# MTQHub.net
KiCad netlist of a schematic drawn in EAGLE
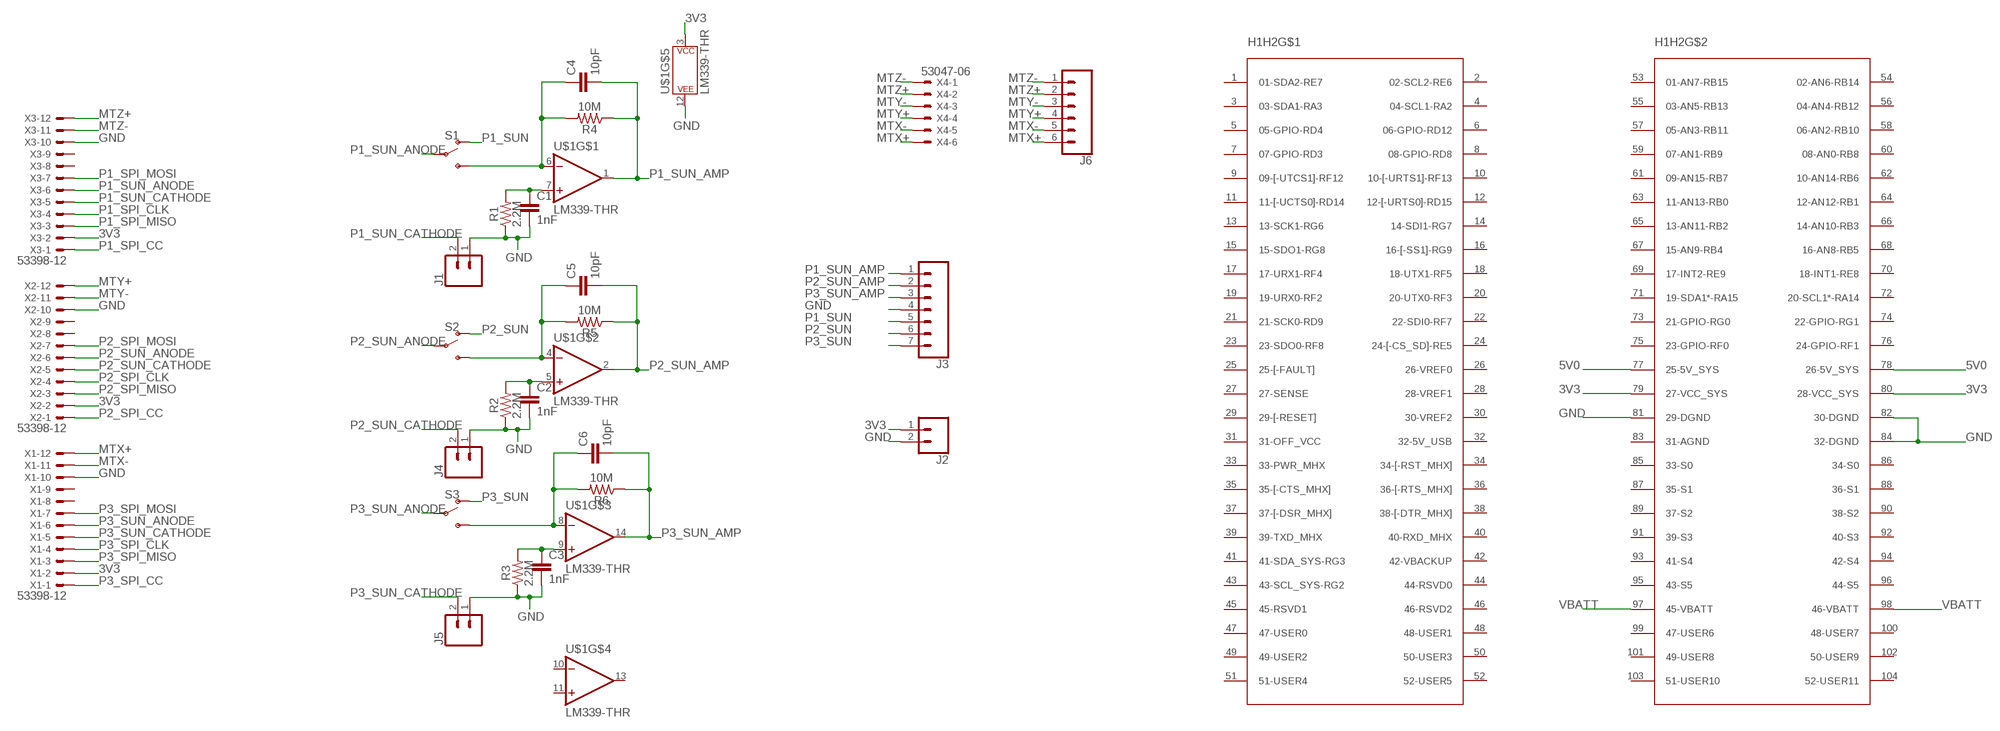
[diagram p0: schematic, sheet 1]

(export (version "E")
  (design (tool "Eeschema 10.0.6"))
  (components
    (comp (ref "C1")
      (value "1nF")
      (footprint "eagle-import:0603")
      (libsource (lib "eagle-import") (part "1.0NF/1000PF-0603-50V-10%"))
    )
    (comp (ref "C2")
      (value "1nF")
      (footprint "eagle-import:0603")
      (libsource (lib "eagle-import") (part "1.0NF/1000PF-0603-50V-10%"))
    )
    (comp (ref "C3")
      (value "1nF")
      (footprint "eagle-import:0603")
      (libsource (lib "eagle-import") (part "1.0NF/1000PF-0603-50V-10%"))
    )
    (comp (ref "C4")
      (value "10pF")
      (footprint "eagle-import:0603")
      (libsource (lib "eagle-import") (part "10PF-0603-50V-5%"))
    )
    (comp (ref "C5")
      (value "10pF")
      (footprint "eagle-import:0603")
      (libsource (lib "eagle-import") (part "10PF-0603-50V-5%"))
    )
    (comp (ref "C6")
      (value "10pF")
      (footprint "eagle-import:0603")
      (libsource (lib "eagle-import") (part "10PF-0603-50V-5%"))
    )
    (comp (ref "H1H2")
      (value "PC104_CONN")
      (footprint "eagle-import:PC_104")
      (libsource (lib "eagle-import") (part "PC104_CONN"))
    )
    (comp (ref "J1")
      (value "CONN_02")
      (footprint "eagle-import:1X02")
      (libsource (lib "eagle-import") (part "CONN_02"))
    )
    (comp (ref "J2")
      (value "CONN_02")
      (footprint "eagle-import:1X02")
      (libsource (lib "eagle-import") (part "CONN_02"))
    )
    (comp (ref "J3")
      (value "CONN_07")
      (footprint "eagle-import:1X07")
      (libsource (lib "eagle-import") (part "CONN_07"))
    )
    (comp (ref "J4")
      (value "CONN_02")
      (footprint "eagle-import:1X02")
      (libsource (lib "eagle-import") (part "CONN_02"))
    )
    (comp (ref "J5")
      (value "CONN_02")
      (footprint "eagle-import:1X02")
      (libsource (lib "eagle-import") (part "CONN_02"))
    )
    (comp (ref "J6")
      (value "CONN_06SILK_FEMALE_PTH")
      (footprint "eagle-import:1X06")
      (libsource (lib "eagle-import") (part "CONN_06SILK_FEMALE_PTH"))
    )
    (comp (ref "R1")
      (value "2.2M")
      (footprint "eagle-import:0603")
      (libsource (lib "eagle-import") (part "RESISTOR0603"))
    )
    (comp (ref "R2")
      (value "2.2M")
      (footprint "eagle-import:0603")
      (libsource (lib "eagle-import") (part "RESISTOR0603"))
    )
    (comp (ref "R3")
      (value "2.2M")
      (footprint "eagle-import:0603")
      (libsource (lib "eagle-import") (part "RESISTOR0603"))
    )
    (comp (ref "R4")
      (value "10M")
      (footprint "eagle-import:0603")
      (libsource (lib "eagle-import") (part "RESISTOR0603"))
    )
    (comp (ref "R5")
      (value "10M")
      (footprint "eagle-import:0603")
      (libsource (lib "eagle-import") (part "RESISTOR0603"))
    )
    (comp (ref "R6")
      (value "10M")
      (footprint "eagle-import:0603")
      (libsource (lib "eagle-import") (part "RESISTOR0603"))
    )
    (comp (ref "S1")
      (value "SWITCH-SPDT-PTH-11.6X4.0MM")
      (footprint "eagle-import:SWITCH_SPDT_PTH_11.6X4.0MM")
      (libsource (lib "eagle-import") (part "SWITCH-SPDT-PTH-11.6X4.0MM"))
    )
    (comp (ref "S2")
      (value "SWITCH-SPDT-PTH-11.6X4.0MM")
      (footprint "eagle-import:SWITCH_SPDT_PTH_11.6X4.0MM")
      (libsource (lib "eagle-import") (part "SWITCH-SPDT-PTH-11.6X4.0MM"))
    )
    (comp (ref "S3")
      (value "SWITCH-SPDT-PTH-11.6X4.0MM")
      (footprint "eagle-import:SWITCH_SPDT_PTH_11.6X4.0MM")
      (libsource (lib "eagle-import") (part "SWITCH-SPDT-PTH-11.6X4.0MM"))
    )
    (comp (ref "U$1")
      (value "LM339-THR")
      (footprint "eagle-import:DIL14")
      (libsource (lib "eagle-import") (part "LM339-THR"))
    )
    (comp (ref "X1")
      (value "53398-12")
      (footprint "eagle-import:53398-12")
      (fields (field (name "MF") "MOLEX"))
      (libsource (lib "eagle-import") (part "53?-12398"))
    )
    (comp (ref "X2")
      (value "53398-12")
      (footprint "eagle-import:53398-12")
      (fields (field (name "MF") "MOLEX"))
      (libsource (lib "eagle-import") (part "53?-12398"))
    )
    (comp (ref "X3")
      (value "53398-12")
      (footprint "eagle-import:53398-12")
      (fields (field (name "MF") "MOLEX"))
      (libsource (lib "eagle-import") (part "53?-12398"))
    )
    (comp (ref "X4")
      (value "53047-06")
      (footprint "eagle-import:53047-06")
      (fields (field (name "MF") "MOLEX") (field (name "MPN") "53047-0610-C"))
      (libsource (lib "eagle-import") (part "53?-06047"))
    )
  )
  (nets
    (net (code "1") (name "/3V3") (class "Default")
      (node (ref "H1H2") (pin "79") (pinfunction "27-VCC_SYS_79") (pintype "bidirectional"))
      (node (ref "H1H2") (pin "80") (pinfunction "28-VCC_SYS_80") (pintype "bidirectional"))
      (node (ref "J2") (pin "1") (pinfunction "1_1") (pintype "passive"))
      (node (ref "U$1") (pin "3") (pinfunction "P$V+_3") (pintype "bidirectional"))
      (node (ref "X1") (pin "2") (pinfunction "S_2") (pintype "passive"))
      (node (ref "X2") (pin "2") (pinfunction "S_2") (pintype "passive"))
      (node (ref "X3") (pin "2") (pinfunction "S_2") (pintype "passive"))
    )
    (net (code "2") (name "/5V0") (class "Default")
      (node (ref "H1H2") (pin "77") (pinfunction "25-5V_SYS_77") (pintype "bidirectional"))
      (node (ref "H1H2") (pin "78") (pinfunction "26-5V_SYS_78") (pintype "bidirectional"))
    )
    (net (code "3") (name "/GND") (class "Default")
      (node (ref "C1") (pin "2") (pinfunction "2_2") (pintype "passive"))
      (node (ref "C2") (pin "2") (pinfunction "2_2") (pintype "passive"))
      (node (ref "C3") (pin "2") (pinfunction "2_2") (pintype "passive"))
      (node (ref "H1H2") (pin "81") (pinfunction "29-DGND_81") (pintype "bidirectional"))
      (node (ref "H1H2") (pin "82") (pinfunction "30-DGND_82") (pintype "bidirectional"))
      (node (ref "H1H2") (pin "84") (pinfunction "32-DGND_84") (pintype "bidirectional"))
      (node (ref "J1") (pin "1") (pinfunction "1_1") (pintype "passive"))
      (node (ref "J2") (pin "2") (pinfunction "2_2") (pintype "passive"))
      (node (ref "J3") (pin "4") (pinfunction "4_4") (pintype "passive"))
      (node (ref "J4") (pin "1") (pinfunction "1_1") (pintype "passive"))
      (node (ref "J5") (pin "1") (pinfunction "1_1") (pintype "passive"))
      (node (ref "R1") (pin "1") (pinfunction "1_1") (pintype "passive"))
      (node (ref "R2") (pin "1") (pinfunction "1_1") (pintype "passive"))
      (node (ref "R3") (pin "1") (pinfunction "1_1") (pintype "passive"))
      (node (ref "U$1") (pin "12") (pinfunction "P$V-_12") (pintype "bidirectional"))
      (node (ref "X1") (pin "10") (pinfunction "S_10") (pintype "passive"))
      (node (ref "X2") (pin "10") (pinfunction "S_10") (pintype "passive"))
      (node (ref "X3") (pin "10") (pinfunction "S_10") (pintype "passive"))
    )
    (net (code "4") (name "/MTX+") (class "Default")
      (node (ref "J6") (pin "6") (pinfunction "6_6") (pintype "passive"))
      (node (ref "X1") (pin "12") (pinfunction "S_12") (pintype "passive"))
      (node (ref "X4") (pin "6") (pinfunction "S_6") (pintype "passive"))
    )
    (net (code "5") (name "/MTX-") (class "Default")
      (node (ref "J6") (pin "5") (pinfunction "5_5") (pintype "passive"))
      (node (ref "X1") (pin "11") (pinfunction "S_11") (pintype "passive"))
      (node (ref "X4") (pin "5") (pinfunction "S_5") (pintype "passive"))
    )
    (net (code "6") (name "/MTY+") (class "Default")
      (node (ref "J6") (pin "4") (pinfunction "4_4") (pintype "passive"))
      (node (ref "X2") (pin "12") (pinfunction "S_12") (pintype "passive"))
      (node (ref "X4") (pin "4") (pinfunction "S_4") (pintype "passive"))
    )
    (net (code "7") (name "/MTY-") (class "Default")
      (node (ref "J6") (pin "3") (pinfunction "3_3") (pintype "passive"))
      (node (ref "X2") (pin "11") (pinfunction "S_11") (pintype "passive"))
      (node (ref "X4") (pin "3") (pinfunction "S_3") (pintype "passive"))
    )
    (net (code "8") (name "/MTZ+") (class "Default")
      (node (ref "J6") (pin "2") (pinfunction "2_2") (pintype "passive"))
      (node (ref "X3") (pin "12") (pinfunction "S_12") (pintype "passive"))
      (node (ref "X4") (pin "2") (pinfunction "S_2") (pintype "passive"))
    )
    (net (code "9") (name "/MTZ-") (class "Default")
      (node (ref "J6") (pin "1") (pinfunction "1_1") (pintype "passive"))
      (node (ref "X3") (pin "11") (pinfunction "S_11") (pintype "passive"))
      (node (ref "X4") (pin "1") (pinfunction "S_1") (pintype "passive"))
    )
    (net (code "10") (name "/P1_SPI_CC") (class "Default")
      (node (ref "X3") (pin "1") (pinfunction "S_1") (pintype "passive"))
    )
    (net (code "11") (name "/P1_SPI_CLK") (class "Default")
      (node (ref "X3") (pin "4") (pinfunction "S_4") (pintype "passive"))
    )
    (net (code "12") (name "/P1_SPI_MISO") (class "Default")
      (node (ref "X3") (pin "3") (pinfunction "S_3") (pintype "passive"))
    )
    (net (code "13") (name "/P1_SPI_MOSI") (class "Default")
      (node (ref "X3") (pin "7") (pinfunction "S_7") (pintype "passive"))
    )
    (net (code "14") (name "/P1_SUN") (class "Default")
      (node (ref "J3") (pin "5") (pinfunction "5_5") (pintype "passive"))
      (node (ref "S1") (pin "1") (pinfunction "O_1") (pintype "passive"))
    )
    (net (code "15") (name "/P1_SUN_AMP") (class "Default")
      (node (ref "C4") (pin "2") (pinfunction "2_2") (pintype "passive"))
      (node (ref "J3") (pin "1") (pinfunction "1_1") (pintype "passive"))
      (node (ref "R4") (pin "1") (pinfunction "1_1") (pintype "passive"))
      (node (ref "U$1") (pin "1") (pinfunction "OUT_1") (pintype "output"))
    )
    (net (code "16") (name "/P1_SUN_ANODE") (class "Default")
      (node (ref "S1") (pin "2") (pinfunction "P_2") (pintype "passive"))
      (node (ref "X3") (pin "6") (pinfunction "S_6") (pintype "passive"))
    )
    (net (code "17") (name "/P1_SUN_CATHODE") (class "Default")
      (node (ref "J1") (pin "2") (pinfunction "2_2") (pintype "passive"))
      (node (ref "X3") (pin "5") (pinfunction "S_5") (pintype "passive"))
    )
    (net (code "18") (name "/P2_SPI_CC") (class "Default")
      (node (ref "X2") (pin "1") (pinfunction "S_1") (pintype "passive"))
    )
    (net (code "19") (name "/P2_SPI_CLK") (class "Default")
      (node (ref "X2") (pin "4") (pinfunction "S_4") (pintype "passive"))
    )
    (net (code "20") (name "/P2_SPI_MISO") (class "Default")
      (node (ref "X2") (pin "3") (pinfunction "S_3") (pintype "passive"))
    )
    (net (code "21") (name "/P2_SPI_MOSI") (class "Default")
      (node (ref "X2") (pin "7") (pinfunction "S_7") (pintype "passive"))
    )
    (net (code "22") (name "/P2_SUN") (class "Default")
      (node (ref "J3") (pin "6") (pinfunction "6_6") (pintype "passive"))
      (node (ref "S2") (pin "1") (pinfunction "O_1") (pintype "passive"))
    )
    (net (code "23") (name "/P2_SUN_AMP") (class "Default")
      (node (ref "C5") (pin "2") (pinfunction "2_2") (pintype "passive"))
      (node (ref "J3") (pin "2") (pinfunction "2_2") (pintype "passive"))
      (node (ref "R5") (pin "1") (pinfunction "1_1") (pintype "passive"))
      (node (ref "U$1") (pin "2") (pinfunction "OUT_2") (pintype "output"))
    )
    (net (code "24") (name "/P2_SUN_ANODE") (class "Default")
      (node (ref "S2") (pin "2") (pinfunction "P_2") (pintype "passive"))
      (node (ref "X2") (pin "6") (pinfunction "S_6") (pintype "passive"))
    )
    (net (code "25") (name "/P2_SUN_CATHODE") (class "Default")
      (node (ref "J4") (pin "2") (pinfunction "2_2") (pintype "passive"))
      (node (ref "X2") (pin "5") (pinfunction "S_5") (pintype "passive"))
    )
    (net (code "26") (name "/P3_SPI_CC") (class "Default")
      (node (ref "X1") (pin "1") (pinfunction "S_1") (pintype "passive"))
    )
    (net (code "27") (name "/P3_SPI_CLK") (class "Default")
      (node (ref "X1") (pin "4") (pinfunction "S_4") (pintype "passive"))
    )
    (net (code "28") (name "/P3_SPI_MISO") (class "Default")
      (node (ref "X1") (pin "3") (pinfunction "S_3") (pintype "passive"))
    )
    (net (code "29") (name "/P3_SPI_MOSI") (class "Default")
      (node (ref "X1") (pin "7") (pinfunction "S_7") (pintype "passive"))
    )
    (net (code "30") (name "/P3_SUN") (class "Default")
      (node (ref "J3") (pin "7") (pinfunction "7_7") (pintype "passive"))
      (node (ref "S3") (pin "1") (pinfunction "O_1") (pintype "passive"))
    )
    (net (code "31") (name "/P3_SUN_AMP") (class "Default")
      (node (ref "C6") (pin "2") (pinfunction "2_2") (pintype "passive"))
      (node (ref "J3") (pin "3") (pinfunction "3_3") (pintype "passive"))
      (node (ref "R6") (pin "1") (pinfunction "1_1") (pintype "passive"))
      (node (ref "U$1") (pin "14") (pinfunction "OUT_14") (pintype "output"))
    )
    (net (code "32") (name "/P3_SUN_ANODE") (class "Default")
      (node (ref "S3") (pin "2") (pinfunction "P_2") (pintype "passive"))
      (node (ref "X1") (pin "6") (pinfunction "S_6") (pintype "passive"))
    )
    (net (code "33") (name "/P3_SUN_CATHODE") (class "Default")
      (node (ref "J5") (pin "2") (pinfunction "2_2") (pintype "passive"))
      (node (ref "X1") (pin "5") (pinfunction "S_5") (pintype "passive"))
    )
    (net (code "34") (name "/VBATT") (class "Default")
      (node (ref "H1H2") (pin "97") (pinfunction "45-VBATT_97") (pintype "bidirectional"))
      (node (ref "H1H2") (pin "98") (pinfunction "46-VBATT_98") (pintype "bidirectional"))
    )
    (net (code "35") (name "Net-(S1-S)") (class "Default")
      (node (ref "C4") (pin "1") (pinfunction "1_1") (pintype "passive"))
      (node (ref "R4") (pin "2") (pinfunction "2_2") (pintype "passive"))
      (node (ref "S1") (pin "3") (pinfunction "S_3") (pintype "passive"))
      (node (ref "U$1") (pin "6") (pinfunction "-IN_6") (pintype "input"))
    )
    (net (code "36") (name "Net-(S2-S)") (class "Default")
      (node (ref "C5") (pin "1") (pinfunction "1_1") (pintype "passive"))
      (node (ref "R5") (pin "2") (pinfunction "2_2") (pintype "passive"))
      (node (ref "S2") (pin "3") (pinfunction "S_3") (pintype "passive"))
      (node (ref "U$1") (pin "4") (pinfunction "-IN_4") (pintype "input"))
    )
    (net (code "37") (name "Net-(S3-S)") (class "Default")
      (node (ref "C6") (pin "1") (pinfunction "1_1") (pintype "passive"))
      (node (ref "R6") (pin "2") (pinfunction "2_2") (pintype "passive"))
      (node (ref "S3") (pin "3") (pinfunction "S_3") (pintype "passive"))
      (node (ref "U$1") (pin "8") (pinfunction "-IN_8") (pintype "input"))
    )
    (net (code "38") (name "Net-(U$1A-+IN)") (class "Default")
      (node (ref "C1") (pin "1") (pinfunction "1_1") (pintype "passive"))
      (node (ref "R1") (pin "2") (pinfunction "2_2") (pintype "passive"))
      (node (ref "U$1") (pin "7") (pinfunction "+IN_7") (pintype "input"))
    )
    (net (code "39") (name "Net-(U$1B-+IN)") (class "Default")
      (node (ref "C2") (pin "1") (pinfunction "1_1") (pintype "passive"))
      (node (ref "R2") (pin "2") (pinfunction "2_2") (pintype "passive"))
      (node (ref "U$1") (pin "5") (pinfunction "+IN_5") (pintype "input"))
    )
    (net (code "40") (name "Net-(U$1C-+IN)") (class "Default")
      (node (ref "C3") (pin "1") (pinfunction "1_1") (pintype "passive"))
      (node (ref "R3") (pin "2") (pinfunction "2_2") (pintype "passive"))
      (node (ref "U$1") (pin "9") (pinfunction "+IN_9") (pintype "input"))
    )
    (net (code "41") (name "unconnected-(H1H2A-01-SDA2-RE7-Pad1)") (class "Default")
      (node (ref "H1H2") (pin "1") (pinfunction "01-SDA2-RE7_1") (pintype "bidirectional"))
    )
    (net (code "42") (name "unconnected-(H1H2A-02-SCL2-RE6-Pad2)") (class "Default")
      (node (ref "H1H2") (pin "2") (pinfunction "02-SCL2-RE6_2") (pintype "bidirectional"))
    )
    (net (code "43") (name "unconnected-(H1H2A-03-SDA1-RA3-Pad3)") (class "Default")
      (node (ref "H1H2") (pin "3") (pinfunction "03-SDA1-RA3_3") (pintype "bidirectional"))
    )
    (net (code "44") (name "unconnected-(H1H2A-04-SCL1-RA2-Pad4)") (class "Default")
      (node (ref "H1H2") (pin "4") (pinfunction "04-SCL1-RA2_4") (pintype "bidirectional"))
    )
    (net (code "45") (name "unconnected-(H1H2A-05-GPIO-RD4-Pad5)") (class "Default")
      (node (ref "H1H2") (pin "5") (pinfunction "05-GPIO-RD4_5") (pintype "bidirectional"))
    )
    (net (code "46") (name "unconnected-(H1H2A-06-GPIO-RD12-Pad6)") (class "Default")
      (node (ref "H1H2") (pin "6") (pinfunction "06-GPIO-RD12_6") (pintype "bidirectional"))
    )
    (net (code "47") (name "unconnected-(H1H2A-07-GPIO-RD3-Pad7)") (class "Default")
      (node (ref "H1H2") (pin "7") (pinfunction "07-GPIO-RD3_7") (pintype "bidirectional"))
    )
    (net (code "48") (name "unconnected-(H1H2A-08-GPIO-RD8-Pad8)") (class "Default")
      (node (ref "H1H2") (pin "8") (pinfunction "08-GPIO-RD8_8") (pintype "bidirectional"))
    )
    (net (code "49") (name "unconnected-(H1H2A-09-[-UTCS1]-RF12-Pad9)") (class "Default")
      (node (ref "H1H2") (pin "9") (pinfunction "09-[-UTCS1]-RF12_9") (pintype "bidirectional"))
    )
    (net (code "50") (name "unconnected-(H1H2A-10-[-URTS1]-RF13-Pad10)") (class "Default")
      (node (ref "H1H2") (pin "10") (pinfunction "10-[-URTS1]-RF13_10") (pintype "bidirectional"))
    )
    (net (code "51") (name "unconnected-(H1H2A-11-[-UCTS0]-RD14-Pad11)") (class "Default")
      (node (ref "H1H2") (pin "11") (pinfunction "11-[-UCTS0]-RD14_11") (pintype "bidirectional"))
    )
    (net (code "52") (name "unconnected-(H1H2A-12-[-URTS0]-RD15-Pad12)") (class "Default")
      (node (ref "H1H2") (pin "12") (pinfunction "12-[-URTS0]-RD15_12") (pintype "bidirectional"))
    )
    (net (code "53") (name "unconnected-(H1H2A-13-SCK1-RG6-Pad13)") (class "Default")
      (node (ref "H1H2") (pin "13") (pinfunction "13-SCK1-RG6_13") (pintype "bidirectional"))
    )
    (net (code "54") (name "unconnected-(H1H2A-14-SDI1-RG7-Pad14)") (class "Default")
      (node (ref "H1H2") (pin "14") (pinfunction "14-SDI1-RG7_14") (pintype "bidirectional"))
    )
    (net (code "55") (name "unconnected-(H1H2A-15-SDO1-RG8-Pad15)") (class "Default")
      (node (ref "H1H2") (pin "15") (pinfunction "15-SDO1-RG8_15") (pintype "bidirectional"))
    )
    (net (code "56") (name "unconnected-(H1H2A-16-[-SS1]-RG9-Pad16)") (class "Default")
      (node (ref "H1H2") (pin "16") (pinfunction "16-[-SS1]-RG9_16") (pintype "bidirectional"))
    )
    (net (code "57") (name "unconnected-(H1H2A-17-URX1-RF4-Pad17)") (class "Default")
      (node (ref "H1H2") (pin "17") (pinfunction "17-URX1-RF4_17") (pintype "bidirectional"))
    )
    (net (code "58") (name "unconnected-(H1H2A-18-UTX1-RF5-Pad18)") (class "Default")
      (node (ref "H1H2") (pin "18") (pinfunction "18-UTX1-RF5_18") (pintype "bidirectional"))
    )
    (net (code "59") (name "unconnected-(H1H2A-19-URX0-RF2-Pad19)") (class "Default")
      (node (ref "H1H2") (pin "19") (pinfunction "19-URX0-RF2_19") (pintype "bidirectional"))
    )
    (net (code "60") (name "unconnected-(H1H2A-20-UTX0-RF3-Pad20)") (class "Default")
      (node (ref "H1H2") (pin "20") (pinfunction "20-UTX0-RF3_20") (pintype "bidirectional"))
    )
    (net (code "61") (name "unconnected-(H1H2A-21-SCK0-RD9-Pad21)") (class "Default")
      (node (ref "H1H2") (pin "21") (pinfunction "21-SCK0-RD9_21") (pintype "bidirectional"))
    )
    (net (code "62") (name "unconnected-(H1H2A-22-SDI0-RF7-Pad22)") (class "Default")
      (node (ref "H1H2") (pin "22") (pinfunction "22-SDI0-RF7_22") (pintype "bidirectional"))
    )
    (net (code "63") (name "unconnected-(H1H2A-23-SDO0-RF8-Pad23)") (class "Default")
      (node (ref "H1H2") (pin "23") (pinfunction "23-SDO0-RF8_23") (pintype "bidirectional"))
    )
    (net (code "64") (name "unconnected-(H1H2A-24-[-CS_SD]-RE5-Pad24)") (class "Default")
      (node (ref "H1H2") (pin "24") (pinfunction "24-[-CS_SD]-RE5_24") (pintype "bidirectional"))
    )
    (net (code "65") (name "unconnected-(H1H2A-25-[-FAULT]-Pad25)") (class "Default")
      (node (ref "H1H2") (pin "25") (pinfunction "25-[-FAULT]_25") (pintype "bidirectional"))
    )
    (net (code "66") (name "unconnected-(H1H2A-26-VREF0-Pad26)") (class "Default")
      (node (ref "H1H2") (pin "26") (pinfunction "26-VREF0_26") (pintype "bidirectional"))
    )
    (net (code "67") (name "unconnected-(H1H2A-27-SENSE-Pad27)") (class "Default")
      (node (ref "H1H2") (pin "27") (pinfunction "27-SENSE_27") (pintype "bidirectional"))
    )
    (net (code "68") (name "unconnected-(H1H2A-28-VREF1-Pad28)") (class "Default")
      (node (ref "H1H2") (pin "28") (pinfunction "28-VREF1_28") (pintype "bidirectional"))
    )
    (net (code "69") (name "unconnected-(H1H2A-29-[-RESET]-Pad29)") (class "Default")
      (node (ref "H1H2") (pin "29") (pinfunction "29-[-RESET]_29") (pintype "bidirectional"))
    )
    (net (code "70") (name "unconnected-(H1H2A-30-VREF2-Pad30)") (class "Default")
      (node (ref "H1H2") (pin "30") (pinfunction "30-VREF2_30") (pintype "bidirectional"))
    )
    (net (code "71") (name "unconnected-(H1H2A-31-OFF_VCC-Pad31)") (class "Default")
      (node (ref "H1H2") (pin "31") (pinfunction "31-OFF_VCC_31") (pintype "bidirectional"))
    )
    (net (code "72") (name "unconnected-(H1H2A-32-5V_USB-Pad32)") (class "Default")
      (node (ref "H1H2") (pin "32") (pinfunction "32-5V_USB_32") (pintype "bidirectional"))
    )
    (net (code "73") (name "unconnected-(H1H2A-33-PWR_MHX-Pad33)") (class "Default")
      (node (ref "H1H2") (pin "33") (pinfunction "33-PWR_MHX_33") (pintype "bidirectional"))
    )
    (net (code "74") (name "unconnected-(H1H2A-34-[-RST_MHX]-Pad34)") (class "Default")
      (node (ref "H1H2") (pin "34") (pinfunction "34-[-RST_MHX]_34") (pintype "bidirectional"))
    )
    (net (code "75") (name "unconnected-(H1H2A-35-[-CTS_MHX]-Pad35)") (class "Default")
      (node (ref "H1H2") (pin "35") (pinfunction "35-[-CTS_MHX]_35") (pintype "bidirectional"))
    )
    (net (code "76") (name "unconnected-(H1H2A-36-[-RTS_MHX]-Pad36)") (class "Default")
      (node (ref "H1H2") (pin "36") (pinfunction "36-[-RTS_MHX]_36") (pintype "bidirectional"))
    )
    (net (code "77") (name "unconnected-(H1H2A-37-[-DSR_MHX]-Pad37)") (class "Default")
      (node (ref "H1H2") (pin "37") (pinfunction "37-[-DSR_MHX]_37") (pintype "bidirectional"))
    )
    (net (code "78") (name "unconnected-(H1H2A-38-[-DTR_MHX]-Pad38)") (class "Default")
      (node (ref "H1H2") (pin "38") (pinfunction "38-[-DTR_MHX]_38") (pintype "bidirectional"))
    )
    (net (code "79") (name "unconnected-(H1H2A-39-TXD_MHX-Pad39)") (class "Default")
      (node (ref "H1H2") (pin "39") (pinfunction "39-TXD_MHX_39") (pintype "bidirectional"))
    )
    (net (code "80") (name "unconnected-(H1H2A-40-RXD_MHX-Pad40)") (class "Default")
      (node (ref "H1H2") (pin "40") (pinfunction "40-RXD_MHX_40") (pintype "bidirectional"))
    )
    (net (code "81") (name "unconnected-(H1H2A-41-SDA_SYS-RG3-Pad41)") (class "Default")
      (node (ref "H1H2") (pin "41") (pinfunction "41-SDA_SYS-RG3_41") (pintype "bidirectional"))
    )
    (net (code "82") (name "unconnected-(H1H2A-42-VBACKUP-Pad42)") (class "Default")
      (node (ref "H1H2") (pin "42") (pinfunction "42-VBACKUP_42") (pintype "bidirectional"))
    )
    (net (code "83") (name "unconnected-(H1H2A-43-SCL_SYS-RG2-Pad43)") (class "Default")
      (node (ref "H1H2") (pin "43") (pinfunction "43-SCL_SYS-RG2_43") (pintype "bidirectional"))
    )
    (net (code "84") (name "unconnected-(H1H2A-44-RSVD0-Pad44)") (class "Default")
      (node (ref "H1H2") (pin "44") (pinfunction "44-RSVD0_44") (pintype "bidirectional"))
    )
    (net (code "85") (name "unconnected-(H1H2A-45-RSVD1-Pad45)") (class "Default")
      (node (ref "H1H2") (pin "45") (pinfunction "45-RSVD1_45") (pintype "bidirectional"))
    )
    (net (code "86") (name "unconnected-(H1H2A-46-RSVD2-Pad46)") (class "Default")
      (node (ref "H1H2") (pin "46") (pinfunction "46-RSVD2_46") (pintype "bidirectional"))
    )
    (net (code "87") (name "unconnected-(H1H2A-47-USER0-Pad47)") (class "Default")
      (node (ref "H1H2") (pin "47") (pinfunction "47-USER0_47") (pintype "bidirectional"))
    )
    (net (code "88") (name "unconnected-(H1H2A-48-USER1-Pad48)") (class "Default")
      (node (ref "H1H2") (pin "48") (pinfunction "48-USER1_48") (pintype "bidirectional"))
    )
    (net (code "89") (name "unconnected-(H1H2A-49-USER2-Pad49)") (class "Default")
      (node (ref "H1H2") (pin "49") (pinfunction "49-USER2_49") (pintype "bidirectional"))
    )
    (net (code "90") (name "unconnected-(H1H2A-50-USER3-Pad50)") (class "Default")
      (node (ref "H1H2") (pin "50") (pinfunction "50-USER3_50") (pintype "bidirectional"))
    )
    (net (code "91") (name "unconnected-(H1H2A-51-USER4-Pad51)") (class "Default")
      (node (ref "H1H2") (pin "51") (pinfunction "51-USER4_51") (pintype "bidirectional"))
    )
    (net (code "92") (name "unconnected-(H1H2A-52-USER5-Pad52)") (class "Default")
      (node (ref "H1H2") (pin "52") (pinfunction "52-USER5_52") (pintype "bidirectional"))
    )
    (net (code "93") (name "unconnected-(H1H2B-01-AN7-RB15-Pad53)") (class "Default")
      (node (ref "H1H2") (pin "53") (pinfunction "01-AN7-RB15_53") (pintype "bidirectional"))
    )
    (net (code "94") (name "unconnected-(H1H2B-02-AN6-RB14-Pad54)") (class "Default")
      (node (ref "H1H2") (pin "54") (pinfunction "02-AN6-RB14_54") (pintype "bidirectional"))
    )
    (net (code "95") (name "unconnected-(H1H2B-03-AN5-RB13-Pad55)") (class "Default")
      (node (ref "H1H2") (pin "55") (pinfunction "03-AN5-RB13_55") (pintype "bidirectional"))
    )
    (net (code "96") (name "unconnected-(H1H2B-04-AN4-RB12-Pad56)") (class "Default")
      (node (ref "H1H2") (pin "56") (pinfunction "04-AN4-RB12_56") (pintype "bidirectional"))
    )
    (net (code "97") (name "unconnected-(H1H2B-05-AN3-RB11-Pad57)") (class "Default")
      (node (ref "H1H2") (pin "57") (pinfunction "05-AN3-RB11_57") (pintype "bidirectional"))
    )
    (net (code "98") (name "unconnected-(H1H2B-06-AN2-RB10-Pad58)") (class "Default")
      (node (ref "H1H2") (pin "58") (pinfunction "06-AN2-RB10_58") (pintype "bidirectional"))
    )
    (net (code "99") (name "unconnected-(H1H2B-07-AN1-RB9-Pad59)") (class "Default")
      (node (ref "H1H2") (pin "59") (pinfunction "07-AN1-RB9_59") (pintype "bidirectional"))
    )
    (net (code "100") (name "unconnected-(H1H2B-08-AN0-RB8-Pad60)") (class "Default")
      (node (ref "H1H2") (pin "60") (pinfunction "08-AN0-RB8_60") (pintype "bidirectional"))
    )
    (net (code "101") (name "unconnected-(H1H2B-09-AN15-RB7-Pad61)") (class "Default")
      (node (ref "H1H2") (pin "61") (pinfunction "09-AN15-RB7_61") (pintype "bidirectional"))
    )
    (net (code "102") (name "unconnected-(H1H2B-10-AN14-RB6-Pad62)") (class "Default")
      (node (ref "H1H2") (pin "62") (pinfunction "10-AN14-RB6_62") (pintype "bidirectional"))
    )
    (net (code "103") (name "unconnected-(H1H2B-11-AN13-RB0-Pad63)") (class "Default")
      (node (ref "H1H2") (pin "63") (pinfunction "11-AN13-RB0_63") (pintype "bidirectional"))
    )
    (net (code "104") (name "unconnected-(H1H2B-12-AN12-RB1-Pad64)") (class "Default")
      (node (ref "H1H2") (pin "64") (pinfunction "12-AN12-RB1_64") (pintype "bidirectional"))
    )
    (net (code "105") (name "unconnected-(H1H2B-13-AN11-RB2-Pad65)") (class "Default")
      (node (ref "H1H2") (pin "65") (pinfunction "13-AN11-RB2_65") (pintype "bidirectional"))
    )
    (net (code "106") (name "unconnected-(H1H2B-14-AN10-RB3-Pad66)") (class "Default")
      (node (ref "H1H2") (pin "66") (pinfunction "14-AN10-RB3_66") (pintype "bidirectional"))
    )
    (net (code "107") (name "unconnected-(H1H2B-15-AN9-RB4-Pad67)") (class "Default")
      (node (ref "H1H2") (pin "67") (pinfunction "15-AN9-RB4_67") (pintype "bidirectional"))
    )
    (net (code "108") (name "unconnected-(H1H2B-16-AN8-RB5-Pad68)") (class "Default")
      (node (ref "H1H2") (pin "68") (pinfunction "16-AN8-RB5_68") (pintype "bidirectional"))
    )
    (net (code "109") (name "unconnected-(H1H2B-17-INT2-RE9-Pad69)") (class "Default")
      (node (ref "H1H2") (pin "69") (pinfunction "17-INT2-RE9_69") (pintype "bidirectional"))
    )
    (net (code "110") (name "unconnected-(H1H2B-18-INT1-RE8-Pad70)") (class "Default")
      (node (ref "H1H2") (pin "70") (pinfunction "18-INT1-RE8_70") (pintype "bidirectional"))
    )
    (net (code "111") (name "unconnected-(H1H2B-19-SDA1*-RA15-Pad71)") (class "Default")
      (node (ref "H1H2") (pin "71") (pinfunction "19-SDA1*-RA15_71") (pintype "bidirectional"))
    )
    (net (code "112") (name "unconnected-(H1H2B-20-SCL1*-RA14-Pad72)") (class "Default")
      (node (ref "H1H2") (pin "72") (pinfunction "20-SCL1*-RA14_72") (pintype "bidirectional"))
    )
    (net (code "113") (name "unconnected-(H1H2B-21-GPIO-RG0-Pad73)") (class "Default")
      (node (ref "H1H2") (pin "73") (pinfunction "21-GPIO-RG0_73") (pintype "bidirectional"))
    )
    (net (code "114") (name "unconnected-(H1H2B-22-GPIO-RG1-Pad74)") (class "Default")
      (node (ref "H1H2") (pin "74") (pinfunction "22-GPIO-RG1_74") (pintype "bidirectional"))
    )
    (net (code "115") (name "unconnected-(H1H2B-23-GPIO-RF0-Pad75)") (class "Default")
      (node (ref "H1H2") (pin "75") (pinfunction "23-GPIO-RF0_75") (pintype "bidirectional"))
    )
    (net (code "116") (name "unconnected-(H1H2B-24-GPIO-RF1-Pad76)") (class "Default")
      (node (ref "H1H2") (pin "76") (pinfunction "24-GPIO-RF1_76") (pintype "bidirectional"))
    )
    (net (code "117") (name "unconnected-(H1H2B-31-AGND-Pad83)") (class "Default")
      (node (ref "H1H2") (pin "83") (pinfunction "31-AGND_83") (pintype "bidirectional"))
    )
    (net (code "118") (name "unconnected-(H1H2B-33-S0-Pad85)") (class "Default")
      (node (ref "H1H2") (pin "85") (pinfunction "33-S0_85") (pintype "bidirectional"))
    )
    (net (code "119") (name "unconnected-(H1H2B-34-S0-Pad86)") (class "Default")
      (node (ref "H1H2") (pin "86") (pinfunction "34-S0_86") (pintype "bidirectional"))
    )
    (net (code "120") (name "unconnected-(H1H2B-35-S1-Pad87)") (class "Default")
      (node (ref "H1H2") (pin "87") (pinfunction "35-S1_87") (pintype "bidirectional"))
    )
    (net (code "121") (name "unconnected-(H1H2B-36-S1-Pad88)") (class "Default")
      (node (ref "H1H2") (pin "88") (pinfunction "36-S1_88") (pintype "bidirectional"))
    )
    (net (code "122") (name "unconnected-(H1H2B-37-S2-Pad89)") (class "Default")
      (node (ref "H1H2") (pin "89") (pinfunction "37-S2_89") (pintype "bidirectional"))
    )
    (net (code "123") (name "unconnected-(H1H2B-38-S2-Pad90)") (class "Default")
      (node (ref "H1H2") (pin "90") (pinfunction "38-S2_90") (pintype "bidirectional"))
    )
    (net (code "124") (name "unconnected-(H1H2B-39-S3-Pad91)") (class "Default")
      (node (ref "H1H2") (pin "91") (pinfunction "39-S3_91") (pintype "bidirectional"))
    )
    (net (code "125") (name "unconnected-(H1H2B-40-S3-Pad92)") (class "Default")
      (node (ref "H1H2") (pin "92") (pinfunction "40-S3_92") (pintype "bidirectional"))
    )
    (net (code "126") (name "unconnected-(H1H2B-41-S4-Pad93)") (class "Default")
      (node (ref "H1H2") (pin "93") (pinfunction "41-S4_93") (pintype "bidirectional"))
    )
    (net (code "127") (name "unconnected-(H1H2B-42-S4-Pad94)") (class "Default")
      (node (ref "H1H2") (pin "94") (pinfunction "42-S4_94") (pintype "bidirectional"))
    )
    (net (code "128") (name "unconnected-(H1H2B-43-S5-Pad95)") (class "Default")
      (node (ref "H1H2") (pin "95") (pinfunction "43-S5_95") (pintype "bidirectional"))
    )
    (net (code "129") (name "unconnected-(H1H2B-44-S5-Pad96)") (class "Default")
      (node (ref "H1H2") (pin "96") (pinfunction "44-S5_96") (pintype "bidirectional"))
    )
    (net (code "130") (name "unconnected-(H1H2B-47-USER6-Pad99)") (class "Default")
      (node (ref "H1H2") (pin "99") (pinfunction "47-USER6_99") (pintype "bidirectional"))
    )
    (net (code "131") (name "unconnected-(H1H2B-48-USER7-Pad100)") (class "Default")
      (node (ref "H1H2") (pin "100") (pinfunction "48-USER7_100") (pintype "bidirectional"))
    )
    (net (code "132") (name "unconnected-(H1H2B-49-USER8-Pad101)") (class "Default")
      (node (ref "H1H2") (pin "101") (pinfunction "49-USER8_101") (pintype "bidirectional"))
    )
    (net (code "133") (name "unconnected-(H1H2B-50-USER9-Pad102)") (class "Default")
      (node (ref "H1H2") (pin "102") (pinfunction "50-USER9_102") (pintype "bidirectional"))
    )
    (net (code "134") (name "unconnected-(H1H2B-51-USER10-Pad103)") (class "Default")
      (node (ref "H1H2") (pin "103") (pinfunction "51-USER10_103") (pintype "bidirectional"))
    )
    (net (code "135") (name "unconnected-(H1H2B-52-USER11-Pad104)") (class "Default")
      (node (ref "H1H2") (pin "104") (pinfunction "52-USER11_104") (pintype "bidirectional"))
    )
    (net (code "136") (name "unconnected-(U$1D-+IN-Pad11)") (class "Default")
      (node (ref "U$1") (pin "11") (pinfunction "+IN_11") (pintype "input"))
    )
    (net (code "137") (name "unconnected-(U$1D--IN-Pad10)") (class "Default")
      (node (ref "U$1") (pin "10") (pinfunction "-IN_10") (pintype "input"))
    )
    (net (code "138") (name "unconnected-(U$1D-OUT-Pad13)") (class "Default")
      (node (ref "U$1") (pin "13") (pinfunction "OUT_13") (pintype "output"))
    )
    (net (code "139") (name "unconnected-(X1K-S-Pad8)") (class "Default")
      (node (ref "X1") (pin "8") (pinfunction "S_8") (pintype "passive"))
    )
    (net (code "140") (name "unconnected-(X1L-S-Pad9)") (class "Default")
      (node (ref "X1") (pin "9") (pinfunction "S_9") (pintype "passive"))
    )
    (net (code "141") (name "unconnected-(X2K-S-Pad8)") (class "Default")
      (node (ref "X2") (pin "8") (pinfunction "S_8") (pintype "passive"))
    )
    (net (code "142") (name "unconnected-(X2L-S-Pad9)") (class "Default")
      (node (ref "X2") (pin "9") (pinfunction "S_9") (pintype "passive"))
    )
    (net (code "143") (name "unconnected-(X3K-S-Pad8)") (class "Default")
      (node (ref "X3") (pin "8") (pinfunction "S_8") (pintype "passive"))
    )
    (net (code "144") (name "unconnected-(X3L-S-Pad9)") (class "Default")
      (node (ref "X3") (pin "9") (pinfunction "S_9") (pintype "passive"))
    )
  )
)
